# LED_Matrix_3_5_tiny.net
KiCad netlist of a schematic drawn in EAGLE
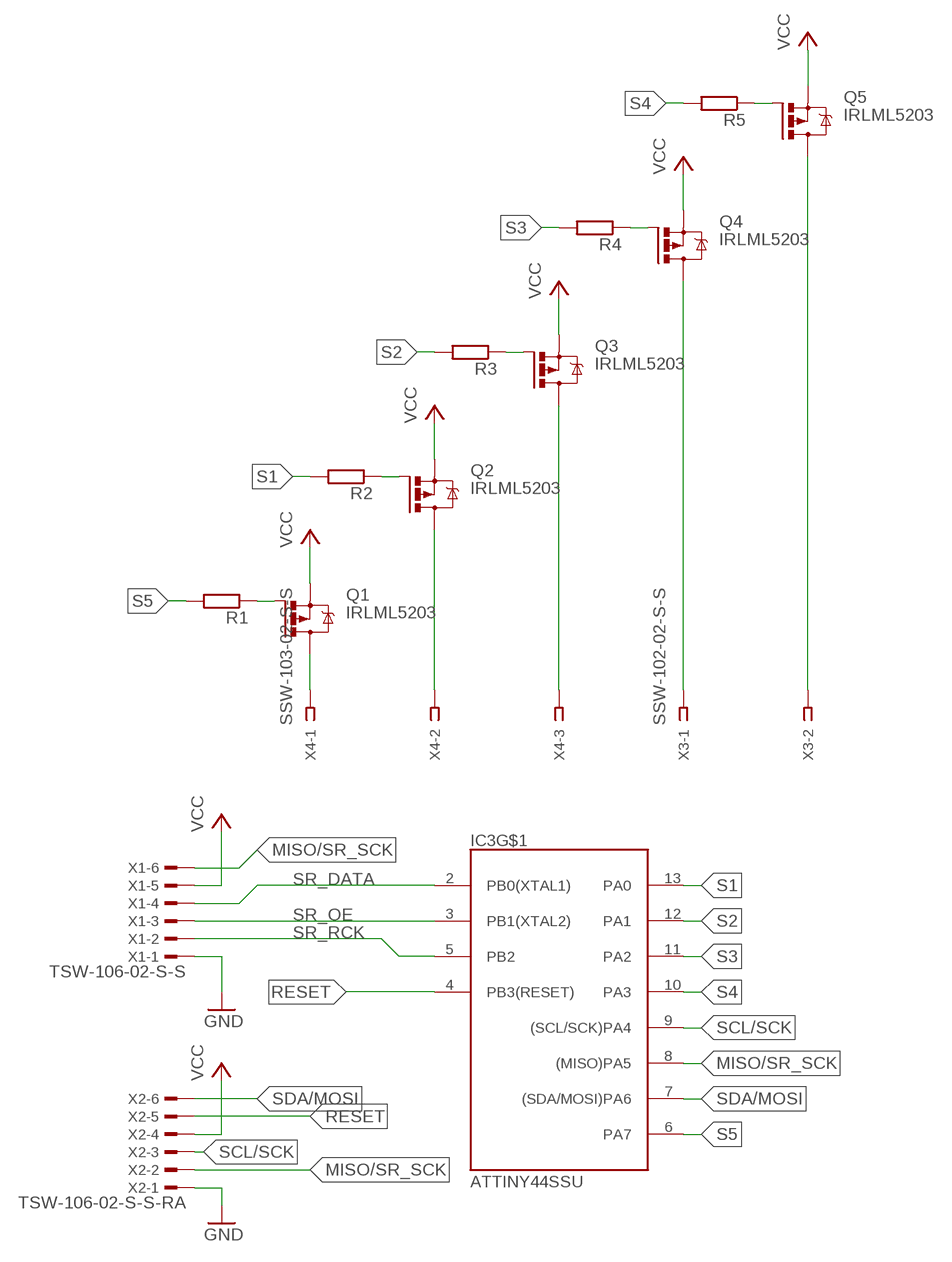
[diagram p0: schematic, sheet 1]

(export (version "E")
  (design (tool "Eeschema 10.0.6"))
  (components
    (comp (ref "IC3")
      (value "ATTINY44SSU")
      (footprint "eagle-import:SO14")
      (libsource (lib "eagle-import") (part "ATTINY44SSU"))
    )
    (comp (ref "Q1")
      (value "IRLML5203")
      (footprint "eagle-import:MICRO3")
      (libsource (lib "eagle-import") (part "IRLML5203"))
    )
    (comp (ref "Q2")
      (value "IRLML5203")
      (footprint "eagle-import:MICRO3")
      (libsource (lib "eagle-import") (part "IRLML5203"))
    )
    (comp (ref "Q3")
      (value "IRLML5203")
      (footprint "eagle-import:MICRO3")
      (libsource (lib "eagle-import") (part "IRLML5203"))
    )
    (comp (ref "Q4")
      (value "IRLML5203")
      (footprint "eagle-import:MICRO3")
      (libsource (lib "eagle-import") (part "IRLML5203"))
    )
    (comp (ref "Q5")
      (value "IRLML5203")
      (footprint "eagle-import:MICRO3")
      (libsource (lib "eagle-import") (part "IRLML5203"))
    )
    (comp (ref "R1")
      (value "R-EU_R0603")
      (footprint "eagle-import:R0603")
      (libsource (lib "eagle-import") (part "R-EU_R0603"))
    )
    (comp (ref "R2")
      (value "R-EU_R0603")
      (footprint "eagle-import:R0603")
      (libsource (lib "eagle-import") (part "R-EU_R0603"))
    )
    (comp (ref "R3")
      (value "R-EU_R0603")
      (footprint "eagle-import:R0603")
      (libsource (lib "eagle-import") (part "R-EU_R0603"))
    )
    (comp (ref "R4")
      (value "R-EU_R0603")
      (footprint "eagle-import:R0603")
      (libsource (lib "eagle-import") (part "R-EU_R0603"))
    )
    (comp (ref "R5")
      (value "R-EU_R0603")
      (footprint "eagle-import:R0603")
      (libsource (lib "eagle-import") (part "R-EU_R0603"))
    )
    (comp (ref "X1")
      (value "TSW-106-02-S-S")
      (footprint "eagle-import:TSW-106-02-S-S")
      (libsource (lib "eagle-import") (part "TSW-106-02-S-S"))
    )
    (comp (ref "X2")
      (value "TSW-106-02-S-S-RA")
      (footprint "eagle-import:TSW-106-02-S-S-RA")
      (libsource (lib "eagle-import") (part "TSW-106-02-S-S-RA"))
    )
    (comp (ref "X3")
      (value "SSW-102-02-S-S")
      (footprint "eagle-import:SSW-102-02-S-S")
      (libsource (lib "eagle-import") (part "SSW-102-02-S-S"))
    )
    (comp (ref "X4")
      (value "SSW-103-02-S-S")
      (footprint "eagle-import:SSW-103-02-S-S")
      (libsource (lib "eagle-import") (part "SSW-103-02-S-S"))
    )
  )
  (nets
    (net (code "1") (name "/SR_DATA") (class "Default")
      (node (ref "IC3") (pin "2") (pinfunction "PB0(XTAL1)_2") (pintype "bidirectional"))
      (node (ref "X1") (pin "4") (pinfunction "1_4") (pintype "passive"))
    )
    (net (code "2") (name "/SR_OE") (class "Default")
      (node (ref "IC3") (pin "3") (pinfunction "PB1(XTAL2)_3") (pintype "bidirectional"))
      (node (ref "X1") (pin "3") (pinfunction "1_3") (pintype "passive"))
    )
    (net (code "3") (name "/SR_RCK") (class "Default")
      (node (ref "IC3") (pin "5") (pinfunction "PB2_5") (pintype "bidirectional"))
      (node (ref "X1") (pin "2") (pinfunction "1_2") (pintype "passive"))
    )
    (net (code "4") (name "GND") (class "Default")
      (node (ref "X1") (pin "1") (pinfunction "1_1") (pintype "passive"))
      (node (ref "X2") (pin "1") (pinfunction "1_1") (pintype "passive"))
    )
    (net (code "5") (name "MISO{slash}SR_SCK") (class "Default")
      (node (ref "IC3") (pin "8") (pinfunction "(MISO)PA5_8") (pintype "bidirectional"))
      (node (ref "X1") (pin "6") (pinfunction "1_6") (pintype "passive"))
      (node (ref "X2") (pin "2") (pinfunction "1_2") (pintype "passive"))
    )
    (net (code "6") (name "Net-(Q1-D)") (class "Default")
      (node (ref "Q1") (pin "3") (pinfunction "D_3") (pintype "passive"))
      (node (ref "X4") (pin "1") (pinfunction "1_1") (pintype "passive"))
    )
    (net (code "7") (name "Net-(Q1-G)") (class "Default")
      (node (ref "Q1") (pin "1") (pinfunction "G_1") (pintype "passive"))
      (node (ref "R1") (pin "1") (pinfunction "1_1") (pintype "passive"))
    )
    (net (code "8") (name "Net-(Q2-D)") (class "Default")
      (node (ref "Q2") (pin "3") (pinfunction "D_3") (pintype "passive"))
      (node (ref "X4") (pin "2") (pinfunction "1_2") (pintype "passive"))
    )
    (net (code "9") (name "Net-(Q2-G)") (class "Default")
      (node (ref "Q2") (pin "1") (pinfunction "G_1") (pintype "passive"))
      (node (ref "R2") (pin "1") (pinfunction "1_1") (pintype "passive"))
    )
    (net (code "10") (name "Net-(Q3-D)") (class "Default")
      (node (ref "Q3") (pin "3") (pinfunction "D_3") (pintype "passive"))
      (node (ref "X4") (pin "3") (pinfunction "1_3") (pintype "passive"))
    )
    (net (code "11") (name "Net-(Q3-G)") (class "Default")
      (node (ref "Q3") (pin "1") (pinfunction "G_1") (pintype "passive"))
      (node (ref "R3") (pin "1") (pinfunction "1_1") (pintype "passive"))
    )
    (net (code "12") (name "Net-(Q4-D)") (class "Default")
      (node (ref "Q4") (pin "3") (pinfunction "D_3") (pintype "passive"))
      (node (ref "X3") (pin "1") (pinfunction "1_1") (pintype "passive"))
    )
    (net (code "13") (name "Net-(Q4-G)") (class "Default")
      (node (ref "Q4") (pin "1") (pinfunction "G_1") (pintype "passive"))
      (node (ref "R4") (pin "1") (pinfunction "1_1") (pintype "passive"))
    )
    (net (code "14") (name "Net-(Q5-D)") (class "Default")
      (node (ref "Q5") (pin "3") (pinfunction "D_3") (pintype "passive"))
      (node (ref "X3") (pin "2") (pinfunction "1_2") (pintype "passive"))
    )
    (net (code "15") (name "Net-(Q5-G)") (class "Default")
      (node (ref "Q5") (pin "1") (pinfunction "G_1") (pintype "passive"))
      (node (ref "R5") (pin "1") (pinfunction "1_1") (pintype "passive"))
    )
    (net (code "16") (name "RESET") (class "Default")
      (node (ref "IC3") (pin "4") (pinfunction "PB3(RESET)_4") (pintype "bidirectional"))
      (node (ref "X2") (pin "5") (pinfunction "1_5") (pintype "passive"))
    )
    (net (code "17") (name "S1") (class "Default")
      (node (ref "IC3") (pin "13") (pinfunction "PA0_13") (pintype "bidirectional"))
      (node (ref "R2") (pin "2") (pinfunction "2_2") (pintype "passive"))
    )
    (net (code "18") (name "S2") (class "Default")
      (node (ref "IC3") (pin "12") (pinfunction "PA1_12") (pintype "bidirectional"))
      (node (ref "R3") (pin "2") (pinfunction "2_2") (pintype "passive"))
    )
    (net (code "19") (name "S3") (class "Default")
      (node (ref "IC3") (pin "11") (pinfunction "PA2_11") (pintype "bidirectional"))
      (node (ref "R4") (pin "2") (pinfunction "2_2") (pintype "passive"))
    )
    (net (code "20") (name "S4") (class "Default")
      (node (ref "IC3") (pin "10") (pinfunction "PA3_10") (pintype "bidirectional"))
      (node (ref "R5") (pin "2") (pinfunction "2_2") (pintype "passive"))
    )
    (net (code "21") (name "S5") (class "Default")
      (node (ref "IC3") (pin "6") (pinfunction "PA7_6") (pintype "bidirectional"))
      (node (ref "R1") (pin "2") (pinfunction "2_2") (pintype "passive"))
    )
    (net (code "22") (name "SCL{slash}SCK") (class "Default")
      (node (ref "IC3") (pin "9") (pinfunction "(SCL/SCK)PA4_9") (pintype "bidirectional"))
      (node (ref "X2") (pin "3") (pinfunction "1_3") (pintype "passive"))
    )
    (net (code "23") (name "SDA{slash}MOSI") (class "Default")
      (node (ref "IC3") (pin "7") (pinfunction "(SDA/MOSI)PA6_7") (pintype "bidirectional"))
      (node (ref "X2") (pin "6") (pinfunction "1_6") (pintype "passive"))
    )
    (net (code "24") (name "VCC") (class "Default")
      (node (ref "Q1") (pin "2") (pinfunction "S_2") (pintype "passive"))
      (node (ref "Q2") (pin "2") (pinfunction "S_2") (pintype "passive"))
      (node (ref "Q3") (pin "2") (pinfunction "S_2") (pintype "passive"))
      (node (ref "Q4") (pin "2") (pinfunction "S_2") (pintype "passive"))
      (node (ref "Q5") (pin "2") (pinfunction "S_2") (pintype "passive"))
      (node (ref "X1") (pin "5") (pinfunction "1_5") (pintype "passive"))
      (node (ref "X2") (pin "4") (pinfunction "1_4") (pintype "passive"))
    )
  )
)
